# ControleEmbalagem.net
KiCad netlist of a schematic drawn in Altium Designer
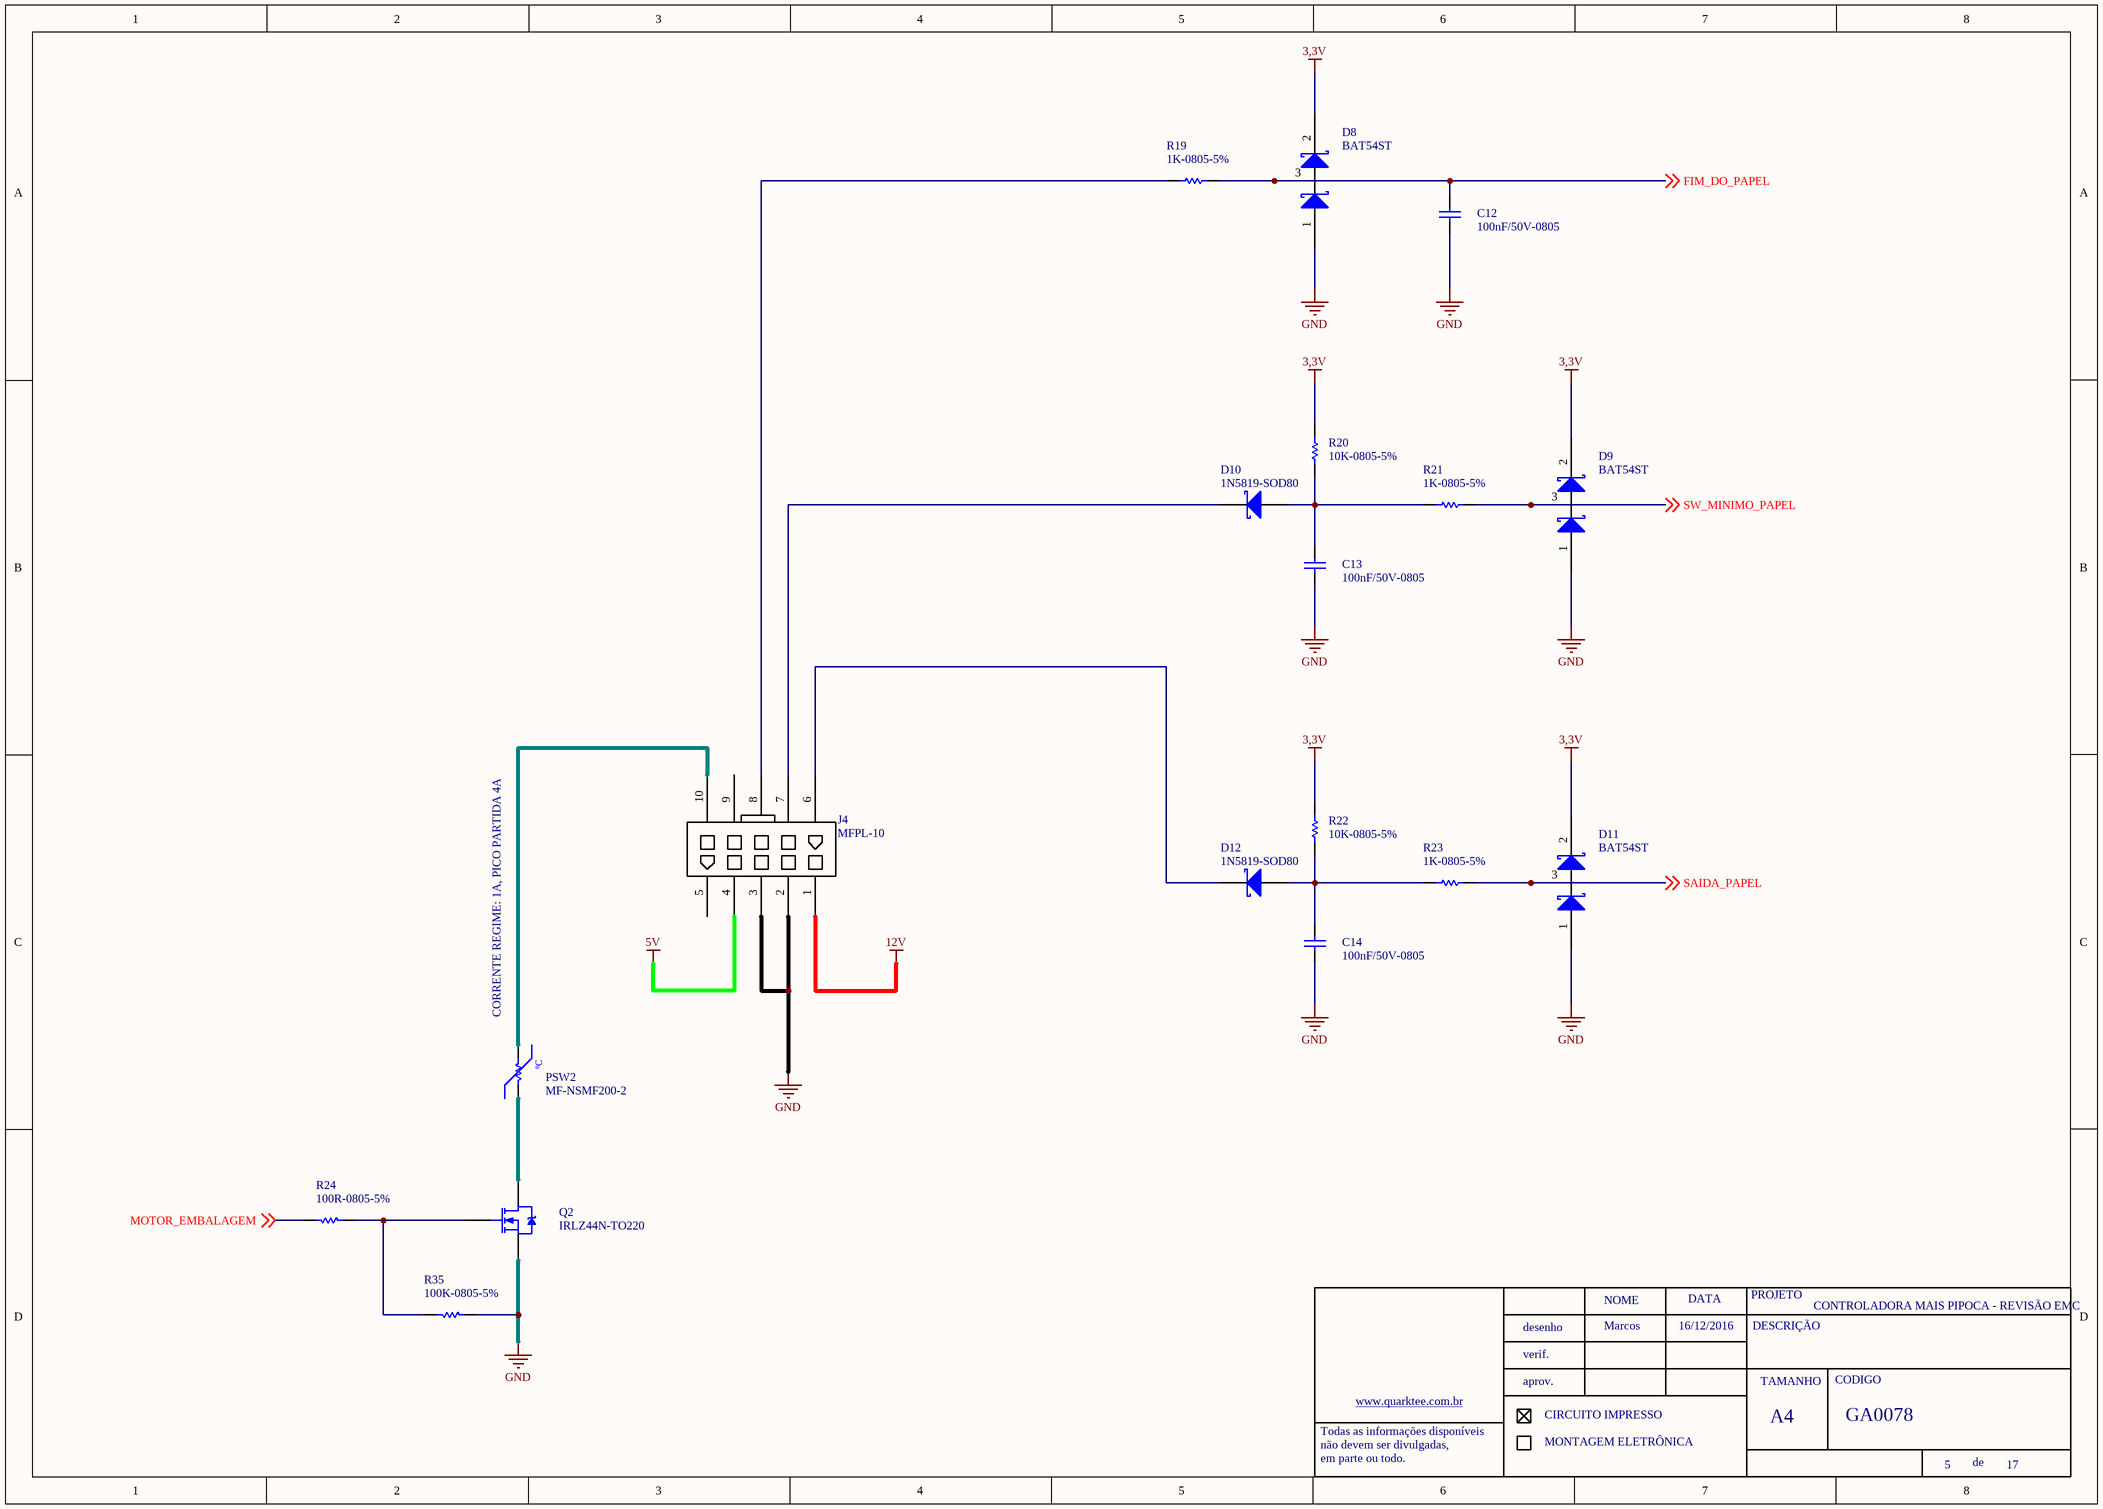
[diagram p0: ControleEmbalagem.SchDoc]

(export (version "E")
  (design (tool "Eeschema 10.0.6"))
  (components
    (comp (ref "C12")
      (value "100nF/50V-0805")
      (footprint "0805-REVISADO ONDA")
      (libsource (lib "AquinoLib") (part "100nF/50-0805-NPO"))
    )
    (comp (ref "C13")
      (value "100nF/50V-0805")
      (footprint "0805-REVISADO ONDA")
      (libsource (lib "AquinoLib") (part "100nF/50-0805-NPO"))
    )
    (comp (ref "C14")
      (value "100nF/50V-0805")
      (footprint "0805-REVISADO ONDA")
      (libsource (lib "AquinoLib") (part "100nF/50-0805-NPO"))
    )
    (comp (ref "D8")
      (value "BAT54ST")
      (footprint "SOT23 - REVISADO ONDA")
      (libsource (lib "AquinoLib") (part "BAT54ST"))
    )
    (comp (ref "D9")
      (value "BAT54ST")
      (footprint "SOT23 - REVISADO ONDA")
      (libsource (lib "AquinoLib") (part "BAT54ST"))
    )
    (comp (ref "D10")
      (value "1N5819-SOD80")
      (footprint "MINIMLEF/SOD80 - REVISADO ONDA")
      (libsource (lib "AquinoLib") (part "1N5819-SOD80"))
    )
    (comp (ref "D11")
      (value "BAT54ST")
      (footprint "SOT23 - REVISADO ONDA")
      (libsource (lib "AquinoLib") (part "BAT54ST"))
    )
    (comp (ref "D12")
      (value "1N5819-SOD80")
      (footprint "MINIMLEF/SOD80 - REVISADO ONDA")
      (libsource (lib "AquinoLib") (part "1N5819-SOD80"))
    )
    (comp (ref "J4") (value "MFPL-10") (libsource (lib "AquinoLib") (part "MFPL-10")))
    (comp (ref "PSW2")
      (value "MF-NSMF200-2")
      (footprint "1206-REVISADO ONDA")
      (description "NANOSMDC020F-2")
      (libsource (lib "AquinoLib") (part "POLYSWITCH 200mA"))
    )
    (comp (ref "Q2")
      (value "IRLZ44N-TO220")
      (footprint "TO220-3 EM PÉ")
      (libsource (lib "ChaveDigital3") (part "IRLZ44N-TO220"))
    )
    (comp (ref "R19")
      (value "1K-0805-5%")
      (footprint "0805-REVISADO ONDA")
      (libsource (lib "AquinoLib") (part "1K-0805-5%"))
    )
    (comp (ref "R20")
      (value "10K-0805-5%")
      (footprint "0805-REVISADO ONDA")
      (libsource (lib "AquinoLib") (part "10K-0805-5%"))
    )
    (comp (ref "R21")
      (value "1K-0805-5%")
      (footprint "0805-REVISADO ONDA")
      (libsource (lib "AquinoLib") (part "1K-0805-5%"))
    )
    (comp (ref "R22")
      (value "10K-0805-5%")
      (footprint "0805-REVISADO ONDA")
      (libsource (lib "AquinoLib") (part "10K-0805-5%"))
    )
    (comp (ref "R23")
      (value "1K-0805-5%")
      (footprint "0805-REVISADO ONDA")
      (libsource (lib "AquinoLib") (part "1K-0805-5%"))
    )
    (comp (ref "R24")
      (value "100R-0805-5%")
      (footprint "0805-REVISADO ONDA")
      (libsource (lib "AquinoLib") (part "100R-0805-5%"))
    )
    (comp (ref "R35")
      (value "100K-0805-5%")
      (footprint "0805-REVISADO ONDA")
      (libsource (lib "AquinoLib") (part "100K-0805-5%"))
    )
  )
  (nets
    (net (code "1") (name "3,3V") (class "Default")
      (node (ref "D11") (pin "2") (pinfunction "2_2") (pintype "passive"))
      (node (ref "D8") (pin "2") (pinfunction "2_2") (pintype "passive"))
      (node (ref "D9") (pin "2") (pinfunction "2_2") (pintype "passive"))
      (node (ref "R20") (pin "2") (pinfunction "2_2") (pintype "passive"))
      (node (ref "R22") (pin "2") (pinfunction "2_2") (pintype "passive"))
    )
    (net (code "2") (name "5V") (class "Default")
      (node (ref "J4") (pin "4") (pinfunction "4_4") (pintype "passive"))
    )
    (net (code "3") (name "12V") (class "Default")
      (node (ref "J4") (pin "1") (pinfunction "1_1") (pintype "passive"))
    )
    (net (code "4") (name "FIM_DO_PAPEL") (class "Default")
      (node (ref "C12") (pin "2") (pinfunction "2_2") (pintype "passive"))
      (node (ref "D8") (pin "3") (pinfunction "3_3") (pintype "passive"))
      (node (ref "R19") (pin "2") (pinfunction "2_2") (pintype "passive"))
    )
    (net (code "5") (name "GND") (class "Default")
      (node (ref "C12") (pin "1") (pinfunction "1_1") (pintype "passive"))
      (node (ref "C13") (pin "1") (pinfunction "1_1") (pintype "passive"))
      (node (ref "C14") (pin "1") (pinfunction "1_1") (pintype "passive"))
      (node (ref "D11") (pin "1") (pinfunction "1_1") (pintype "passive"))
      (node (ref "D8") (pin "1") (pinfunction "1_1") (pintype "passive"))
      (node (ref "D9") (pin "1") (pinfunction "1_1") (pintype "passive"))
      (node (ref "J4") (pin "2") (pinfunction "2_2") (pintype "passive"))
      (node (ref "J4") (pin "3") (pinfunction "3_3") (pintype "passive"))
      (node (ref "Q2") (pin "3") (pinfunction "S_3") (pintype "passive"))
      (node (ref "R35") (pin "1") (pinfunction "1_1") (pintype "passive"))
    )
    (net (code "6") (name "MOTOR_EMBALAGEM") (class "Default")
      (node (ref "R24") (pin "2") (pinfunction "2_2") (pintype "passive"))
    )
    (net (code "7") (name "Net-(D10-A)") (class "Default")
      (node (ref "C13") (pin "2") (pinfunction "2_2") (pintype "passive"))
      (node (ref "D10") (pin "1") (pinfunction "A_1") (pintype "passive"))
      (node (ref "R20") (pin "1") (pinfunction "1_1") (pintype "passive"))
      (node (ref "R21") (pin "1") (pinfunction "1_1") (pintype "passive"))
    )
    (net (code "8") (name "Net-(D10-K)") (class "Default")
      (node (ref "D10") (pin "2") (pinfunction "K_2") (pintype "passive"))
      (node (ref "J4") (pin "7") (pinfunction "7_7") (pintype "passive"))
    )
    (net (code "9") (name "Net-(D12-A)") (class "Default")
      (node (ref "C14") (pin "2") (pinfunction "2_2") (pintype "passive"))
      (node (ref "D12") (pin "1") (pinfunction "A_1") (pintype "passive"))
      (node (ref "R22") (pin "1") (pinfunction "1_1") (pintype "passive"))
      (node (ref "R23") (pin "1") (pinfunction "1_1") (pintype "passive"))
    )
    (net (code "10") (name "Net-(D12-K)") (class "Default")
      (node (ref "D12") (pin "2") (pinfunction "K_2") (pintype "passive"))
      (node (ref "J4") (pin "6") (pinfunction "6_6") (pintype "passive"))
    )
    (net (code "11") (name "Net-(J4-Pad8)") (class "Default")
      (node (ref "J4") (pin "8") (pinfunction "8_8") (pintype "passive"))
      (node (ref "R19") (pin "1") (pinfunction "1_1") (pintype "passive"))
    )
    (net (code "12") (name "Net-(J4-Pad10)") (class "Default")
      (node (ref "J4") (pin "10") (pinfunction "10_10") (pintype "passive"))
      (node (ref "PSW2") (pin "2") (pinfunction "2_2") (pintype "passive"))
    )
    (net (code "13") (name "Net-(Q2-D)") (class "Default")
      (node (ref "PSW2") (pin "1") (pinfunction "1_1") (pintype "passive"))
      (node (ref "Q2") (pin "2") (pinfunction "D_2") (pintype "passive"))
    )
    (net (code "14") (name "Net-(Q2-G)") (class "Default")
      (node (ref "Q2") (pin "1") (pinfunction "G_1") (pintype "passive"))
      (node (ref "R24") (pin "1") (pinfunction "1_1") (pintype "passive"))
      (node (ref "R35") (pin "2") (pinfunction "2_2") (pintype "passive"))
    )
    (net (code "15") (name "SAIDA_PAPEL") (class "Default")
      (node (ref "D11") (pin "3") (pinfunction "3_3") (pintype "passive"))
      (node (ref "R23") (pin "2") (pinfunction "2_2") (pintype "passive"))
    )
    (net (code "16") (name "SW_MINIMO_PAPEL") (class "Default")
      (node (ref "D9") (pin "3") (pinfunction "3_3") (pintype "passive"))
      (node (ref "R21") (pin "2") (pinfunction "2_2") (pintype "passive"))
    )
    (net (code "17") (name "unconnected-(J4-Pad5)") (class "Default")
      (node (ref "J4") (pin "5") (pinfunction "5_5") (pintype "passive"))
    )
    (net (code "18") (name "unconnected-(J4-Pad9)") (class "Default")
      (node (ref "J4") (pin "9") (pinfunction "9_9") (pintype "passive"))
    )
  )
)
